# Camera.net
KiCad netlist of a schematic drawn in Altium Designer
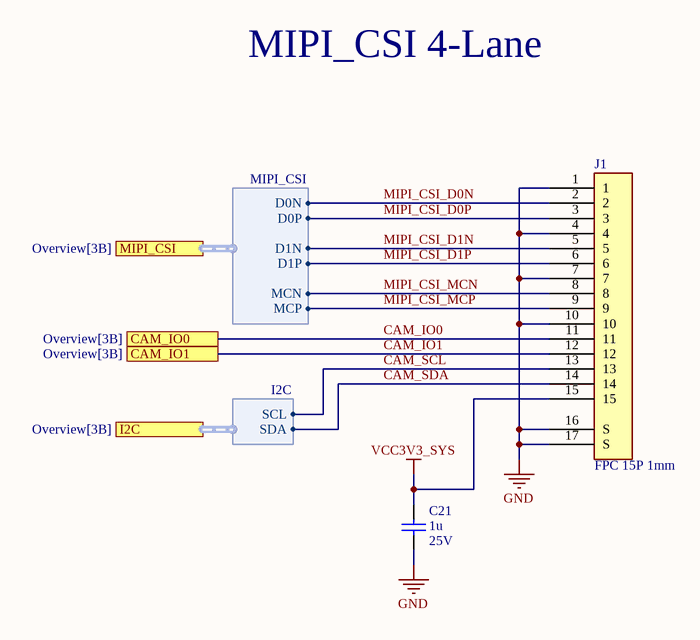
[diagram p0: Camera.SchDoc]

(export (version "E")
  (design (tool "Eeschema 10.0.6"))
  (components
    (comp (ref "C21")
      (value "1u")
      (footprint "GRM155R61E105KA12D")
      (description "CAP 1U 25V X5R 0402")
      (fields (field (name "VOLTAGE") "25V") (field (name "Comment") "GRM155R61E105KA12D"))
      (libsource (lib "PersonalAltiumLibrary") (part "GRM155R61E105KA12D"))
    )
    (comp (ref "J1") (value "FPC 15P 1mm") (libsource (lib "PersonalAltiumLibrary") (part "FPC 15P 1mm")))
  )
  (nets
    (net (code "3") (name "/CAM_IO0") (class "Default")
      (node (ref "J1") (pin "11") (pinfunction "11_11") (pintype "passive"))
    )
    (net (code "4") (name "/CAM_IO1") (class "Default")
      (node (ref "J1") (pin "12") (pinfunction "12_12") (pintype "passive"))
    )
    (net (code "5") (name "/CAM_SCL") (class "Default")
      (node (ref "J1") (pin "13") (pinfunction "13_13") (pintype "passive"))
    )
    (net (code "6") (name "/CAM_SDA") (class "Default")
      (node (ref "J1") (pin "14") (pinfunction "14_14") (pintype "passive"))
    )
    (net (code "7") (name "/MIPI_CSI_D0N") (class "Default")
      (node (ref "J1") (pin "2") (pinfunction "2_2") (pintype "passive"))
    )
    (net (code "8") (name "/MIPI_CSI_D0P") (class "Default")
      (node (ref "J1") (pin "3") (pinfunction "3_3") (pintype "passive"))
    )
    (net (code "9") (name "/MIPI_CSI_D1N") (class "Default")
      (node (ref "J1") (pin "5") (pinfunction "5_5") (pintype "passive"))
    )
    (net (code "10") (name "/MIPI_CSI_D1P") (class "Default")
      (node (ref "J1") (pin "6") (pinfunction "6_6") (pintype "passive"))
    )
    (net (code "11") (name "/MIPI_CSI_MCN") (class "Default")
      (node (ref "J1") (pin "8") (pinfunction "8_8") (pintype "passive"))
    )
    (net (code "12") (name "/MIPI_CSI_MCP") (class "Default")
      (node (ref "J1") (pin "9") (pinfunction "9_9") (pintype "passive"))
    )
    (net (code "15") (name "GND") (class "Default")
      (node (ref "C21") (pin "2") (pinfunction "2_2") (pintype "passive"))
      (node (ref "J1") (pin "1") (pinfunction "1_1") (pintype "passive"))
      (node (ref "J1") (pin "10") (pinfunction "10_10") (pintype "passive"))
      (node (ref "J1") (pin "16") (pinfunction "S_16") (pintype "passive"))
      (node (ref "J1") (pin "17") (pinfunction "S_17") (pintype "passive"))
      (node (ref "J1") (pin "4") (pinfunction "4_4") (pintype "passive"))
      (node (ref "J1") (pin "7") (pinfunction "7_7") (pintype "passive"))
    )
    (net (code "16") (name "VCC3V3_SYS") (class "Default")
      (node (ref "C21") (pin "1") (pinfunction "1_1") (pintype "passive"))
      (node (ref "J1") (pin "15") (pinfunction "15_15") (pintype "passive"))
    )
  )
)
